# main.net
KiCad netlist of a schematic drawn in Altium Designer
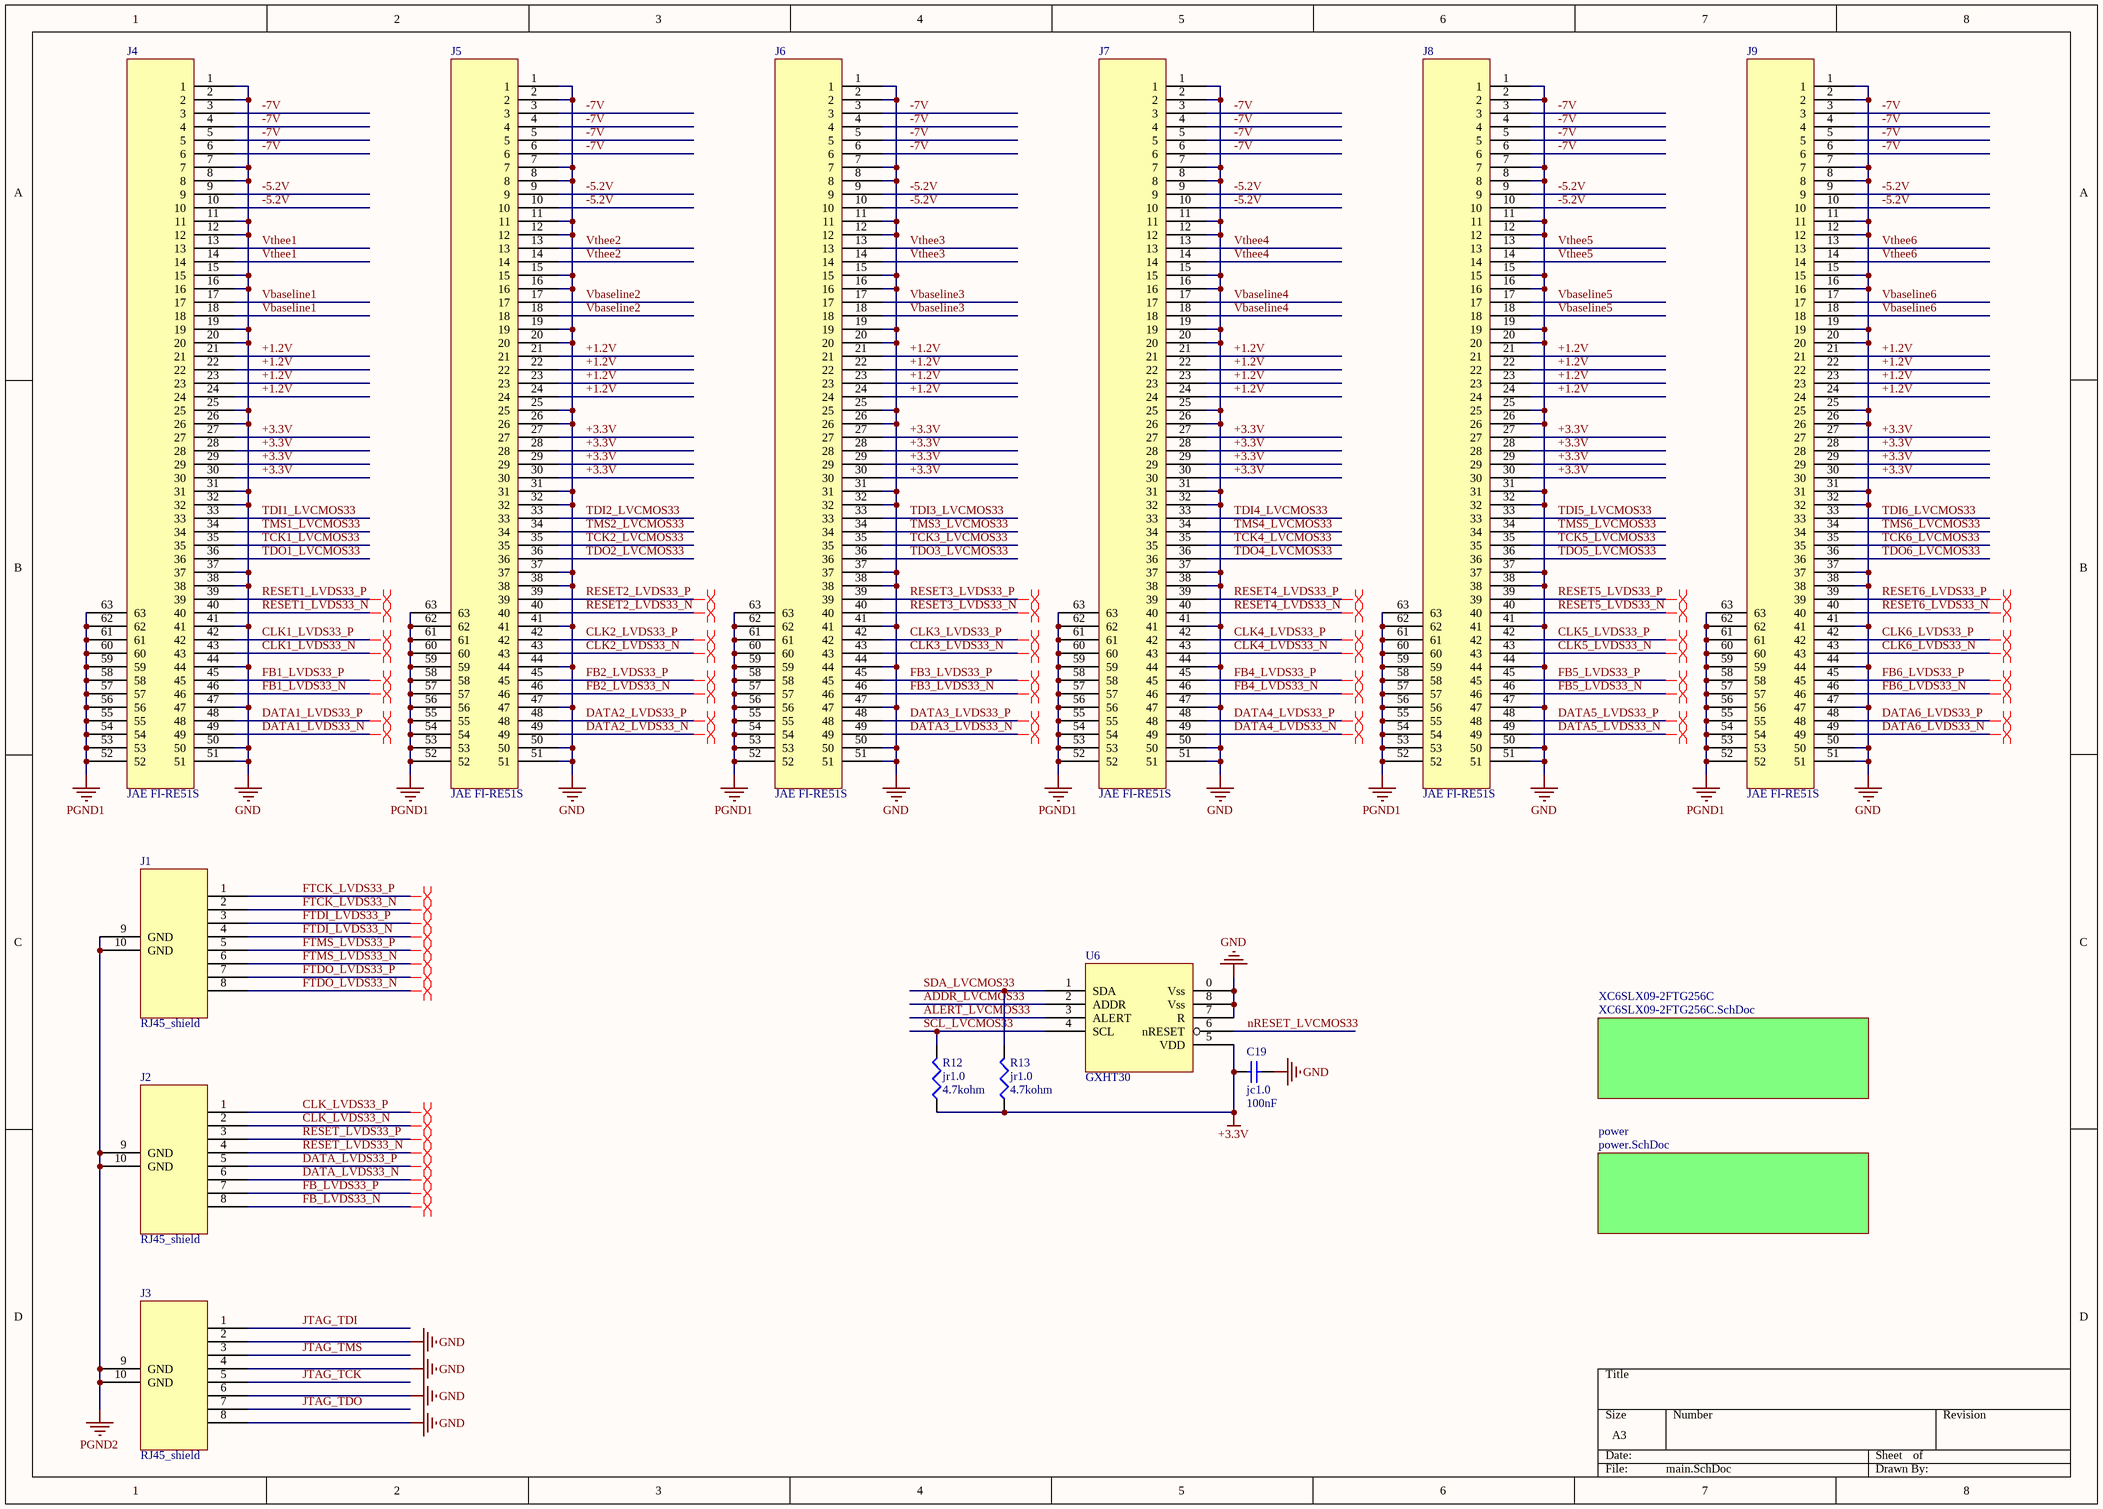
[diagram p0: main.SchDoc]

(export (version "E")
  (design (tool "Eeschema 10.0.6"))
  (components
    (comp (ref "C19")
      (value "jc1.0")
      (footprint "0402")
      (description "Capacitor")
      (fields (field (name "ALTIUM_VALUE") "100nF") (field (name "PUBLISHER") "Altium Limited"))
      (libsource (lib "LIB01DXP2006SchLib") (part "Cap"))
    )
    (comp (ref "J1")
      (value "RJ45_shield")
      (footprint "RJ45_shield")
      (libsource (lib "LIB01DXP2006SchLib") (part "RJ45_shield"))
    )
    (comp (ref "J2")
      (value "RJ45_shield")
      (footprint "RJ45_shield")
      (libsource (lib "LIB01DXP2006SchLib") (part "RJ45_shield"))
    )
    (comp (ref "J3")
      (value "RJ45_shield")
      (footprint "RJ45_shield")
      (libsource (lib "LIB01DXP2006SchLib") (part "RJ45_shield"))
    )
    (comp (ref "J4")
      (value "JAE FI-RE51S")
      (footprint "FI-RE51S-VF")
      (libsource (lib "LIB01DXP2006SchLib") (part "JAE FI-RE51S"))
    )
    (comp (ref "J5")
      (value "JAE FI-RE51S")
      (footprint "FI-RE51S-VF")
      (libsource (lib "LIB01DXP2006SchLib") (part "JAE FI-RE51S"))
    )
    (comp (ref "J6")
      (value "JAE FI-RE51S")
      (footprint "FI-RE51S-VF")
      (libsource (lib "LIB01DXP2006SchLib") (part "JAE FI-RE51S"))
    )
    (comp (ref "J7")
      (value "JAE FI-RE51S")
      (footprint "FI-RE51S-VF")
      (libsource (lib "LIB01DXP2006SchLib") (part "JAE FI-RE51S"))
    )
    (comp (ref "J8")
      (value "JAE FI-RE51S")
      (footprint "FI-RE51S-VF")
      (libsource (lib "LIB01DXP2006SchLib") (part "JAE FI-RE51S"))
    )
    (comp (ref "J9")
      (value "JAE FI-RE51S")
      (footprint "FI-RE51S-VF")
      (libsource (lib "LIB01DXP2006SchLib") (part "JAE FI-RE51S"))
    )
    (comp (ref "R12")
      (value "jr1.0")
      (footprint "0402")
      (description "Resistor")
      (fields (field (name "ALTIUM_VALUE") "4.7kohm") (field (name "PUBLISHER") "Altium Limited"))
      (libsource (lib "LIB01DXP2006SchLib") (part "Res"))
    )
    (comp (ref "R13")
      (value "jr1.0")
      (footprint "0402")
      (description "Resistor")
      (fields (field (name "ALTIUM_VALUE") "4.7kohm") (field (name "PUBLISHER") "Altium Limited"))
      (libsource (lib "LIB01DXP2006SchLib") (part "Res"))
    )
    (comp (ref "U6")
      (value "GXHT30")
      (footprint "GXHT30")
      (libsource (lib "LIB01DXP2006SchLib") (part "GXHT30"))
    )
  )
  (nets
    (net (code "1") (name "+3.3V") (class "Default")
      (node (ref "C19") (pin "1") (pinfunction "1_1") (pintype "passive"))
      (node (ref "J4") (pin "27") (pinfunction "27_27") (pintype "passive"))
      (node (ref "J4") (pin "28") (pinfunction "28_28") (pintype "passive"))
      (node (ref "J4") (pin "29") (pinfunction "29_29") (pintype "passive"))
      (node (ref "J4") (pin "30") (pinfunction "30_30") (pintype "passive"))
      (node (ref "J5") (pin "27") (pinfunction "27_27") (pintype "passive"))
      (node (ref "J5") (pin "28") (pinfunction "28_28") (pintype "passive"))
      (node (ref "J5") (pin "29") (pinfunction "29_29") (pintype "passive"))
      (node (ref "J5") (pin "30") (pinfunction "30_30") (pintype "passive"))
      (node (ref "J6") (pin "27") (pinfunction "27_27") (pintype "passive"))
      (node (ref "J6") (pin "28") (pinfunction "28_28") (pintype "passive"))
      (node (ref "J6") (pin "29") (pinfunction "29_29") (pintype "passive"))
      (node (ref "J6") (pin "30") (pinfunction "30_30") (pintype "passive"))
      (node (ref "J7") (pin "27") (pinfunction "27_27") (pintype "passive"))
      (node (ref "J7") (pin "28") (pinfunction "28_28") (pintype "passive"))
      (node (ref "J7") (pin "29") (pinfunction "29_29") (pintype "passive"))
      (node (ref "J7") (pin "30") (pinfunction "30_30") (pintype "passive"))
      (node (ref "J8") (pin "27") (pinfunction "27_27") (pintype "passive"))
      (node (ref "J8") (pin "28") (pinfunction "28_28") (pintype "passive"))
      (node (ref "J8") (pin "29") (pinfunction "29_29") (pintype "passive"))
      (node (ref "J8") (pin "30") (pinfunction "30_30") (pintype "passive"))
      (node (ref "J9") (pin "27") (pinfunction "27_27") (pintype "passive"))
      (node (ref "J9") (pin "28") (pinfunction "28_28") (pintype "passive"))
      (node (ref "J9") (pin "29") (pinfunction "29_29") (pintype "passive"))
      (node (ref "J9") (pin "30") (pinfunction "30_30") (pintype "passive"))
      (node (ref "R12") (pin "1") (pinfunction "1_1") (pintype "passive"))
      (node (ref "R13") (pin "1") (pinfunction "1_1") (pintype "passive"))
      (node (ref "U6") (pin "5") (pinfunction "VDD_5") (pintype "passive"))
    )
    (net (code "2") (name "/+1.2V") (class "Default")
      (node (ref "J4") (pin "21") (pinfunction "21_21") (pintype "passive"))
      (node (ref "J4") (pin "22") (pinfunction "22_22") (pintype "passive"))
      (node (ref "J4") (pin "23") (pinfunction "23_23") (pintype "passive"))
      (node (ref "J4") (pin "24") (pinfunction "24_24") (pintype "passive"))
      (node (ref "J5") (pin "21") (pinfunction "21_21") (pintype "passive"))
      (node (ref "J5") (pin "22") (pinfunction "22_22") (pintype "passive"))
      (node (ref "J5") (pin "23") (pinfunction "23_23") (pintype "passive"))
      (node (ref "J5") (pin "24") (pinfunction "24_24") (pintype "passive"))
      (node (ref "J6") (pin "21") (pinfunction "21_21") (pintype "passive"))
      (node (ref "J6") (pin "22") (pinfunction "22_22") (pintype "passive"))
      (node (ref "J6") (pin "23") (pinfunction "23_23") (pintype "passive"))
      (node (ref "J6") (pin "24") (pinfunction "24_24") (pintype "passive"))
      (node (ref "J7") (pin "21") (pinfunction "21_21") (pintype "passive"))
      (node (ref "J7") (pin "22") (pinfunction "22_22") (pintype "passive"))
      (node (ref "J7") (pin "23") (pinfunction "23_23") (pintype "passive"))
      (node (ref "J7") (pin "24") (pinfunction "24_24") (pintype "passive"))
      (node (ref "J8") (pin "21") (pinfunction "21_21") (pintype "passive"))
      (node (ref "J8") (pin "22") (pinfunction "22_22") (pintype "passive"))
      (node (ref "J8") (pin "23") (pinfunction "23_23") (pintype "passive"))
      (node (ref "J8") (pin "24") (pinfunction "24_24") (pintype "passive"))
      (node (ref "J9") (pin "21") (pinfunction "21_21") (pintype "passive"))
      (node (ref "J9") (pin "22") (pinfunction "22_22") (pintype "passive"))
      (node (ref "J9") (pin "23") (pinfunction "23_23") (pintype "passive"))
      (node (ref "J9") (pin "24") (pinfunction "24_24") (pintype "passive"))
    )
    (net (code "3") (name "/-5.2V") (class "Default")
      (node (ref "J4") (pin "10") (pinfunction "10_10") (pintype "passive"))
      (node (ref "J4") (pin "9") (pinfunction "9_9") (pintype "passive"))
      (node (ref "J5") (pin "10") (pinfunction "10_10") (pintype "passive"))
      (node (ref "J5") (pin "9") (pinfunction "9_9") (pintype "passive"))
      (node (ref "J6") (pin "10") (pinfunction "10_10") (pintype "passive"))
      (node (ref "J6") (pin "9") (pinfunction "9_9") (pintype "passive"))
      (node (ref "J7") (pin "10") (pinfunction "10_10") (pintype "passive"))
      (node (ref "J7") (pin "9") (pinfunction "9_9") (pintype "passive"))
      (node (ref "J8") (pin "10") (pinfunction "10_10") (pintype "passive"))
      (node (ref "J8") (pin "9") (pinfunction "9_9") (pintype "passive"))
      (node (ref "J9") (pin "10") (pinfunction "10_10") (pintype "passive"))
      (node (ref "J9") (pin "9") (pinfunction "9_9") (pintype "passive"))
    )
    (net (code "4") (name "/-7V") (class "Default")
      (node (ref "J4") (pin "3") (pinfunction "3_3") (pintype "passive"))
      (node (ref "J4") (pin "4") (pinfunction "4_4") (pintype "passive"))
      (node (ref "J4") (pin "5") (pinfunction "5_5") (pintype "passive"))
      (node (ref "J4") (pin "6") (pinfunction "6_6") (pintype "passive"))
      (node (ref "J5") (pin "3") (pinfunction "3_3") (pintype "passive"))
      (node (ref "J5") (pin "4") (pinfunction "4_4") (pintype "passive"))
      (node (ref "J5") (pin "5") (pinfunction "5_5") (pintype "passive"))
      (node (ref "J5") (pin "6") (pinfunction "6_6") (pintype "passive"))
      (node (ref "J6") (pin "3") (pinfunction "3_3") (pintype "passive"))
      (node (ref "J6") (pin "4") (pinfunction "4_4") (pintype "passive"))
      (node (ref "J6") (pin "5") (pinfunction "5_5") (pintype "passive"))
      (node (ref "J6") (pin "6") (pinfunction "6_6") (pintype "passive"))
      (node (ref "J7") (pin "3") (pinfunction "3_3") (pintype "passive"))
      (node (ref "J7") (pin "4") (pinfunction "4_4") (pintype "passive"))
      (node (ref "J7") (pin "5") (pinfunction "5_5") (pintype "passive"))
      (node (ref "J7") (pin "6") (pinfunction "6_6") (pintype "passive"))
      (node (ref "J8") (pin "3") (pinfunction "3_3") (pintype "passive"))
      (node (ref "J8") (pin "4") (pinfunction "4_4") (pintype "passive"))
      (node (ref "J8") (pin "5") (pinfunction "5_5") (pintype "passive"))
      (node (ref "J8") (pin "6") (pinfunction "6_6") (pintype "passive"))
      (node (ref "J9") (pin "3") (pinfunction "3_3") (pintype "passive"))
      (node (ref "J9") (pin "4") (pinfunction "4_4") (pintype "passive"))
      (node (ref "J9") (pin "5") (pinfunction "5_5") (pintype "passive"))
      (node (ref "J9") (pin "6") (pinfunction "6_6") (pintype "passive"))
    )
    (net (code "5") (name "/ADDR_LVCMOS33") (class "Default")
      (node (ref "U6") (pin "2") (pinfunction "ADDR_2") (pintype "passive"))
    )
    (net (code "6") (name "/ALERT_LVCMOS33") (class "Default")
      (node (ref "U6") (pin "3") (pinfunction "ALERT_3") (pintype "passive"))
    )
    (net (code "7") (name "/CLK1_LVDS33_N") (class "Default")
      (node (ref "J4") (pin "43") (pinfunction "43_43") (pintype "passive"))
    )
    (net (code "8") (name "/CLK1_LVDS33_P") (class "Default")
      (node (ref "J4") (pin "42") (pinfunction "42_42") (pintype "passive"))
    )
    (net (code "9") (name "/CLK2_LVDS33_N") (class "Default")
      (node (ref "J5") (pin "43") (pinfunction "43_43") (pintype "passive"))
    )
    (net (code "10") (name "/CLK2_LVDS33_P") (class "Default")
      (node (ref "J5") (pin "42") (pinfunction "42_42") (pintype "passive"))
    )
    (net (code "11") (name "/CLK3_LVDS33_N") (class "Default")
      (node (ref "J6") (pin "43") (pinfunction "43_43") (pintype "passive"))
    )
    (net (code "12") (name "/CLK3_LVDS33_P") (class "Default")
      (node (ref "J6") (pin "42") (pinfunction "42_42") (pintype "passive"))
    )
    (net (code "13") (name "/CLK4_LVDS33_N") (class "Default")
      (node (ref "J7") (pin "43") (pinfunction "43_43") (pintype "passive"))
    )
    (net (code "14") (name "/CLK4_LVDS33_P") (class "Default")
      (node (ref "J7") (pin "42") (pinfunction "42_42") (pintype "passive"))
    )
    (net (code "15") (name "/CLK5_LVDS33_N") (class "Default")
      (node (ref "J8") (pin "43") (pinfunction "43_43") (pintype "passive"))
    )
    (net (code "16") (name "/CLK5_LVDS33_P") (class "Default")
      (node (ref "J8") (pin "42") (pinfunction "42_42") (pintype "passive"))
    )
    (net (code "17") (name "/CLK6_LVDS33_N") (class "Default")
      (node (ref "J9") (pin "43") (pinfunction "43_43") (pintype "passive"))
    )
    (net (code "18") (name "/CLK6_LVDS33_P") (class "Default")
      (node (ref "J9") (pin "42") (pinfunction "42_42") (pintype "passive"))
    )
    (net (code "19") (name "/CLK_LVDS33_N") (class "Default") (node (ref "J2") (pin "2") (pintype "passive")))
    (net (code "20") (name "/CLK_LVDS33_P") (class "Default") (node (ref "J2") (pin "1") (pintype "passive")))
    (net (code "21") (name "/DATA1_LVDS33_N") (class "Default")
      (node (ref "J4") (pin "49") (pinfunction "49_49") (pintype "passive"))
    )
    (net (code "22") (name "/DATA1_LVDS33_P") (class "Default")
      (node (ref "J4") (pin "48") (pinfunction "48_48") (pintype "passive"))
    )
    (net (code "23") (name "/DATA2_LVDS33_N") (class "Default")
      (node (ref "J5") (pin "49") (pinfunction "49_49") (pintype "passive"))
    )
    (net (code "24") (name "/DATA2_LVDS33_P") (class "Default")
      (node (ref "J5") (pin "48") (pinfunction "48_48") (pintype "passive"))
    )
    (net (code "25") (name "/DATA3_LVDS33_N") (class "Default")
      (node (ref "J6") (pin "49") (pinfunction "49_49") (pintype "passive"))
    )
    (net (code "26") (name "/DATA3_LVDS33_P") (class "Default")
      (node (ref "J6") (pin "48") (pinfunction "48_48") (pintype "passive"))
    )
    (net (code "27") (name "/DATA4_LVDS33_N") (class "Default")
      (node (ref "J7") (pin "49") (pinfunction "49_49") (pintype "passive"))
    )
    (net (code "28") (name "/DATA4_LVDS33_P") (class "Default")
      (node (ref "J7") (pin "48") (pinfunction "48_48") (pintype "passive"))
    )
    (net (code "29") (name "/DATA5_LVDS33_N") (class "Default")
      (node (ref "J8") (pin "49") (pinfunction "49_49") (pintype "passive"))
    )
    (net (code "30") (name "/DATA5_LVDS33_P") (class "Default")
      (node (ref "J8") (pin "48") (pinfunction "48_48") (pintype "passive"))
    )
    (net (code "31") (name "/DATA6_LVDS33_N") (class "Default")
      (node (ref "J9") (pin "49") (pinfunction "49_49") (pintype "passive"))
    )
    (net (code "32") (name "/DATA6_LVDS33_P") (class "Default")
      (node (ref "J9") (pin "48") (pinfunction "48_48") (pintype "passive"))
    )
    (net (code "33") (name "/DATA_LVDS33_N") (class "Default")
      (node (ref "J2") (pin "6") (pintype "passive"))
    )
    (net (code "34") (name "/DATA_LVDS33_P") (class "Default")
      (node (ref "J2") (pin "5") (pintype "passive"))
    )
    (net (code "35") (name "/FB1_LVDS33_N") (class "Default")
      (node (ref "J4") (pin "46") (pinfunction "46_46") (pintype "passive"))
    )
    (net (code "36") (name "/FB1_LVDS33_P") (class "Default")
      (node (ref "J4") (pin "45") (pinfunction "45_45") (pintype "passive"))
    )
    (net (code "37") (name "/FB2_LVDS33_N") (class "Default")
      (node (ref "J5") (pin "46") (pinfunction "46_46") (pintype "passive"))
    )
    (net (code "38") (name "/FB2_LVDS33_P") (class "Default")
      (node (ref "J5") (pin "45") (pinfunction "45_45") (pintype "passive"))
    )
    (net (code "39") (name "/FB3_LVDS33_N") (class "Default")
      (node (ref "J6") (pin "46") (pinfunction "46_46") (pintype "passive"))
    )
    (net (code "40") (name "/FB3_LVDS33_P") (class "Default")
      (node (ref "J6") (pin "45") (pinfunction "45_45") (pintype "passive"))
    )
    (net (code "41") (name "/FB4_LVDS33_N") (class "Default")
      (node (ref "J7") (pin "46") (pinfunction "46_46") (pintype "passive"))
    )
    (net (code "42") (name "/FB4_LVDS33_P") (class "Default")
      (node (ref "J7") (pin "45") (pinfunction "45_45") (pintype "passive"))
    )
    (net (code "43") (name "/FB5_LVDS33_N") (class "Default")
      (node (ref "J8") (pin "46") (pinfunction "46_46") (pintype "passive"))
    )
    (net (code "44") (name "/FB5_LVDS33_P") (class "Default")
      (node (ref "J8") (pin "45") (pinfunction "45_45") (pintype "passive"))
    )
    (net (code "45") (name "/FB6_LVDS33_N") (class "Default")
      (node (ref "J9") (pin "46") (pinfunction "46_46") (pintype "passive"))
    )
    (net (code "46") (name "/FB6_LVDS33_P") (class "Default")
      (node (ref "J9") (pin "45") (pinfunction "45_45") (pintype "passive"))
    )
    (net (code "47") (name "/FB_LVDS33_N") (class "Default") (node (ref "J2") (pin "8") (pintype "passive")))
    (net (code "48") (name "/FB_LVDS33_P") (class "Default") (node (ref "J2") (pin "7") (pintype "passive")))
    (net (code "49") (name "/FTCK_LVDS33_N") (class "Default")
      (node (ref "J1") (pin "2") (pintype "passive"))
    )
    (net (code "50") (name "/FTCK_LVDS33_P") (class "Default")
      (node (ref "J1") (pin "1") (pintype "passive"))
    )
    (net (code "51") (name "/FTDI_LVDS33_N") (class "Default")
      (node (ref "J1") (pin "4") (pintype "passive"))
    )
    (net (code "52") (name "/FTDI_LVDS33_P") (class "Default")
      (node (ref "J1") (pin "3") (pintype "passive"))
    )
    (net (code "53") (name "/FTDO_LVDS33_N") (class "Default")
      (node (ref "J1") (pin "8") (pintype "passive"))
    )
    (net (code "54") (name "/FTDO_LVDS33_P") (class "Default")
      (node (ref "J1") (pin "7") (pintype "passive"))
    )
    (net (code "55") (name "/FTMS_LVDS33_N") (class "Default")
      (node (ref "J1") (pin "6") (pintype "passive"))
    )
    (net (code "56") (name "/FTMS_LVDS33_P") (class "Default")
      (node (ref "J1") (pin "5") (pintype "passive"))
    )
    (net (code "57") (name "/JTAG_TCK") (class "Default") (node (ref "J3") (pin "5") (pintype "passive")))
    (net (code "58") (name "/JTAG_TDI") (class "Default") (node (ref "J3") (pin "1") (pintype "passive")))
    (net (code "59") (name "/JTAG_TDO") (class "Default") (node (ref "J3") (pin "7") (pintype "passive")))
    (net (code "60") (name "/JTAG_TMS") (class "Default") (node (ref "J3") (pin "3") (pintype "passive")))
    (net (code "61") (name "/RESET1_LVDS33_N") (class "Default")
      (node (ref "J4") (pin "40") (pinfunction "40_40") (pintype "passive"))
    )
    (net (code "62") (name "/RESET1_LVDS33_P") (class "Default")
      (node (ref "J4") (pin "39") (pinfunction "39_39") (pintype "passive"))
    )
    (net (code "63") (name "/RESET2_LVDS33_N") (class "Default")
      (node (ref "J5") (pin "40") (pinfunction "40_40") (pintype "passive"))
    )
    (net (code "64") (name "/RESET2_LVDS33_P") (class "Default")
      (node (ref "J5") (pin "39") (pinfunction "39_39") (pintype "passive"))
    )
    (net (code "65") (name "/RESET3_LVDS33_N") (class "Default")
      (node (ref "J6") (pin "40") (pinfunction "40_40") (pintype "passive"))
    )
    (net (code "66") (name "/RESET3_LVDS33_P") (class "Default")
      (node (ref "J6") (pin "39") (pinfunction "39_39") (pintype "passive"))
    )
    (net (code "67") (name "/RESET4_LVDS33_N") (class "Default")
      (node (ref "J7") (pin "40") (pinfunction "40_40") (pintype "passive"))
    )
    (net (code "68") (name "/RESET4_LVDS33_P") (class "Default")
      (node (ref "J7") (pin "39") (pinfunction "39_39") (pintype "passive"))
    )
    (net (code "69") (name "/RESET5_LVDS33_N") (class "Default")
      (node (ref "J8") (pin "40") (pinfunction "40_40") (pintype "passive"))
    )
    (net (code "70") (name "/RESET5_LVDS33_P") (class "Default")
      (node (ref "J8") (pin "39") (pinfunction "39_39") (pintype "passive"))
    )
    (net (code "71") (name "/RESET6_LVDS33_N") (class "Default")
      (node (ref "J9") (pin "40") (pinfunction "40_40") (pintype "passive"))
    )
    (net (code "72") (name "/RESET6_LVDS33_P") (class "Default")
      (node (ref "J9") (pin "39") (pinfunction "39_39") (pintype "passive"))
    )
    (net (code "73") (name "/RESET_LVDS33_N") (class "Default")
      (node (ref "J2") (pin "4") (pintype "passive"))
    )
    (net (code "74") (name "/RESET_LVDS33_P") (class "Default")
      (node (ref "J2") (pin "3") (pintype "passive"))
    )
    (net (code "75") (name "/SCL_LVCMOS33") (class "Default")
      (node (ref "R12") (pin "2") (pinfunction "2_2") (pintype "passive"))
      (node (ref "U6") (pin "4") (pinfunction "SCL_4") (pintype "passive"))
    )
    (net (code "76") (name "/SDA_LVCMOS33") (class "Default")
      (node (ref "R13") (pin "2") (pinfunction "2_2") (pintype "passive"))
      (node (ref "U6") (pin "1") (pinfunction "SDA_1") (pintype "passive"))
    )
    (net (code "77") (name "/TCK1_LVCMOS33") (class "Default")
      (node (ref "J4") (pin "35") (pinfunction "35_35") (pintype "passive"))
    )
    (net (code "78") (name "/TCK2_LVCMOS33") (class "Default")
      (node (ref "J5") (pin "35") (pinfunction "35_35") (pintype "passive"))
    )
    (net (code "79") (name "/TCK3_LVCMOS33") (class "Default")
      (node (ref "J6") (pin "35") (pinfunction "35_35") (pintype "passive"))
    )
    (net (code "80") (name "/TCK4_LVCMOS33") (class "Default")
      (node (ref "J7") (pin "35") (pinfunction "35_35") (pintype "passive"))
    )
    (net (code "81") (name "/TCK5_LVCMOS33") (class "Default")
      (node (ref "J8") (pin "35") (pinfunction "35_35") (pintype "passive"))
    )
    (net (code "82") (name "/TCK6_LVCMOS33") (class "Default")
      (node (ref "J9") (pin "35") (pinfunction "35_35") (pintype "passive"))
    )
    (net (code "83") (name "/TDI1_LVCMOS33") (class "Default")
      (node (ref "J4") (pin "33") (pinfunction "33_33") (pintype "passive"))
    )
    (net (code "84") (name "/TDI2_LVCMOS33") (class "Default")
      (node (ref "J5") (pin "33") (pinfunction "33_33") (pintype "passive"))
    )
    (net (code "85") (name "/TDI3_LVCMOS33") (class "Default")
      (node (ref "J6") (pin "33") (pinfunction "33_33") (pintype "passive"))
    )
    (net (code "86") (name "/TDI4_LVCMOS33") (class "Default")
      (node (ref "J7") (pin "33") (pinfunction "33_33") (pintype "passive"))
    )
    (net (code "87") (name "/TDI5_LVCMOS33") (class "Default")
      (node (ref "J8") (pin "33") (pinfunction "33_33") (pintype "passive"))
    )
    (net (code "88") (name "/TDI6_LVCMOS33") (class "Default")
      (node (ref "J9") (pin "33") (pinfunction "33_33") (pintype "passive"))
    )
    (net (code "89") (name "/TDO1_LVCMOS33") (class "Default")
      (node (ref "J4") (pin "36") (pinfunction "36_36") (pintype "passive"))
    )
    (net (code "90") (name "/TDO2_LVCMOS33") (class "Default")
      (node (ref "J5") (pin "36") (pinfunction "36_36") (pintype "passive"))
    )
    (net (code "91") (name "/TDO3_LVCMOS33") (class "Default")
      (node (ref "J6") (pin "36") (pinfunction "36_36") (pintype "passive"))
    )
    (net (code "92") (name "/TDO4_LVCMOS33") (class "Default")
      (node (ref "J7") (pin "36") (pinfunction "36_36") (pintype "passive"))
    )
    (net (code "93") (name "/TDO5_LVCMOS33") (class "Default")
      (node (ref "J8") (pin "36") (pinfunction "36_36") (pintype "passive"))
    )
    (net (code "94") (name "/TDO6_LVCMOS33") (class "Default")
      (node (ref "J9") (pin "36") (pinfunction "36_36") (pintype "passive"))
    )
    (net (code "95") (name "/TMS1_LVCMOS33") (class "Default")
      (node (ref "J4") (pin "34") (pinfunction "34_34") (pintype "passive"))
    )
    (net (code "96") (name "/TMS2_LVCMOS33") (class "Default")
      (node (ref "J5") (pin "34") (pinfunction "34_34") (pintype "passive"))
    )
    (net (code "97") (name "/TMS3_LVCMOS33") (class "Default")
      (node (ref "J6") (pin "34") (pinfunction "34_34") (pintype "passive"))
    )
    (net (code "98") (name "/TMS4_LVCMOS33") (class "Default")
      (node (ref "J7") (pin "34") (pinfunction "34_34") (pintype "passive"))
    )
    (net (code "99") (name "/TMS5_LVCMOS33") (class "Default")
      (node (ref "J8") (pin "34") (pinfunction "34_34") (pintype "passive"))
    )
    (net (code "100") (name "/TMS6_LVCMOS33") (class "Default")
      (node (ref "J9") (pin "34") (pinfunction "34_34") (pintype "passive"))
    )
    (net (code "101") (name "/Vbaseline1") (class "Default")
      (node (ref "J4") (pin "17") (pinfunction "17_17") (pintype "passive"))
      (node (ref "J4") (pin "18") (pinfunction "18_18") (pintype "passive"))
    )
    (net (code "102") (name "/Vbaseline2") (class "Default")
      (node (ref "J5") (pin "17") (pinfunction "17_17") (pintype "passive"))
      (node (ref "J5") (pin "18") (pinfunction "18_18") (pintype "passive"))
    )
    (net (code "103") (name "/Vbaseline3") (class "Default")
      (node (ref "J6") (pin "17") (pinfunction "17_17") (pintype "passive"))
      (node (ref "J6") (pin "18") (pinfunction "18_18") (pintype "passive"))
    )
    (net (code "104") (name "/Vbaseline4") (class "Default")
      (node (ref "J7") (pin "17") (pinfunction "17_17") (pintype "passive"))
      (node (ref "J7") (pin "18") (pinfunction "18_18") (pintype "passive"))
    )
    (net (code "105") (name "/Vbaseline5") (class "Default")
      (node (ref "J8") (pin "17") (pinfunction "17_17") (pintype "passive"))
      (node (ref "J8") (pin "18") (pinfunction "18_18") (pintype "passive"))
    )
    (net (code "106") (name "/Vbaseline6") (class "Default")
      (node (ref "J9") (pin "17") (pinfunction "17_17") (pintype "passive"))
      (node (ref "J9") (pin "18") (pinfunction "18_18") (pintype "passive"))
    )
    (net (code "107") (name "/Vthee1") (class "Default")
      (node (ref "J4") (pin "13") (pinfunction "13_13") (pintype "passive"))
      (node (ref "J4") (pin "14") (pinfunction "14_14") (pintype "passive"))
    )
    (net (code "108") (name "/Vthee2") (class "Default")
      (node (ref "J5") (pin "13") (pinfunction "13_13") (pintype "passive"))
      (node (ref "J5") (pin "14") (pinfunction "14_14") (pintype "passive"))
    )
    (net (code "109") (name "/Vthee3") (class "Default")
      (node (ref "J6") (pin "13") (pinfunction "13_13") (pintype "passive"))
      (node (ref "J6") (pin "14") (pinfunction "14_14") (pintype "passive"))
    )
    (net (code "110") (name "/Vthee4") (class "Default")
      (node (ref "J7") (pin "13") (pinfunction "13_13") (pintype "passive"))
      (node (ref "J7") (pin "14") (pinfunction "14_14") (pintype "passive"))
    )
    (net (code "111") (name "/Vthee5") (class "Default")
      (node (ref "J8") (pin "13") (pinfunction "13_13") (pintype "passive"))
      (node (ref "J8") (pin "14") (pinfunction "14_14") (pintype "passive"))
    )
    (net (code "112") (name "/Vthee6") (class "Default")
      (node (ref "J9") (pin "13") (pinfunction "13_13") (pintype "passive"))
      (node (ref "J9") (pin "14") (pinfunction "14_14") (pintype "passive"))
    )
    (net (code "113") (name "/nRESET_LVCMOS33") (class "Default")
      (node (ref "U6") (pin "6") (pinfunction "nRESET_6") (pintype "passive"))
    )
    (net (code "114") (name "GND") (class "Default")
      (node (ref "C19") (pin "2") (pinfunction "2_2") (pintype "passive"))
      (node (ref "J3") (pin "2") (pintype "passive"))
      (node (ref "J3") (pin "4") (pintype "passive"))
      (node (ref "J3") (pin "6") (pintype "passive"))
      (node (ref "J3") (pin "8") (pintype "passive"))
      (node (ref "J4") (pin "1") (pinfunction "1_1") (pintype "passive"))
      (node (ref "J4") (pin "11") (pinfunction "11_11") (pintype "passive"))
      (node (ref "J4") (pin "12") (pinfunction "12_12") (pintype "passive"))
      (node (ref "J4") (pin "15") (pinfunction "15_15") (pintype "passive"))
      (node (ref "J4") (pin "16") (pinfunction "16_16") (pintype "passive"))
      (node (ref "J4") (pin "19") (pinfunction "19_19") (pintype "passive"))
      (node (ref "J4") (pin "2") (pinfunction "2_2") (pintype "passive"))
      (node (ref "J4") (pin "20") (pinfunction "20_20") (pintype "passive"))
      (node (ref "J4") (pin "25") (pinfunction "25_25") (pintype "passive"))
      (node (ref "J4") (pin "26") (pinfunction "26_26") (pintype "passive"))
      (node (ref "J4") (pin "31") (pinfunction "31_31") (pintype "passive"))
      (node (ref "J4") (pin "32") (pinfunction "32_32") (pintype "passive"))
      (node (ref "J4") (pin "37") (pinfunction "37_37") (pintype "passive"))
      (node (ref "J4") (pin "38") (pinfunction "38_38") (pintype "passive"))
      (node (ref "J4") (pin "41") (pinfunction "41_41") (pintype "passive"))
      (node (ref "J4") (pin "44") (pinfunction "44_44") (pintype "passive"))
      (node (ref "J4") (pin "47") (pinfunction "47_47") (pintype "passive"))
      (node (ref "J4") (pin "50") (pinfunction "50_50") (pintype "passive"))
      (node (ref "J4") (pin "51") (pinfunction "51_51") (pintype "passive"))
      (node (ref "J4") (pin "7") (pinfunction "7_7") (pintype "passive"))
      (node (ref "J4") (pin "8") (pinfunction "8_8") (pintype "passive"))
      (node (ref "J5") (pin "1") (pinfunction "1_1") (pintype "passive"))
      (node (ref "J5") (pin "11") (pinfunction "11_11") (pintype "passive"))
      (node (ref "J5") (pin "12") (pinfunction "12_12") (pintype "passive"))
      (node (ref "J5") (pin "15") (pinfunction "15_15") (pintype "passive"))
      (node (ref "J5") (pin "16") (pinfunction "16_16") (pintype "passive"))
      (node (ref "J5") (pin "19") (pinfunction "19_19") (pintype "passive"))
      (node (ref "J5") (pin "2") (pinfunction "2_2") (pintype "passive"))
      (node (ref "J5") (pin "20") (pinfunction "20_20") (pintype "passive"))
      (node (ref "J5") (pin "25") (pinfunction "25_25") (pintype "passive"))
      (node (ref "J5") (pin "26") (pinfunction "26_26") (pintype "passive"))
      (node (ref "J5") (pin "31") (pinfunction "31_31") (pintype "passive"))
      (node (ref "J5") (pin "32") (pinfunction "32_32") (pintype "passive"))
      (node (ref "J5") (pin "37") (pinfunction "37_37") (pintype "passive"))
      (node (ref "J5") (pin "38") (pinfunction "38_38") (pintype "passive"))
      (node (ref "J5") (pin "41") (pinfunction "41_41") (pintype "passive"))
      (node (ref "J5") (pin "44") (pinfunction "44_44") (pintype "passive"))
      (node (ref "J5") (pin "47") (pinfunction "47_47") (pintype "passive"))
      (node (ref "J5") (pin "50") (pinfunction "50_50") (pintype "passive"))
      (node (ref "J5") (pin "51") (pinfunction "51_51") (pintype "passive"))
      (node (ref "J5") (pin "7") (pinfunction "7_7") (pintype "passive"))
      (node (ref "J5") (pin "8") (pinfunction "8_8") (pintype "passive"))
      (node (ref "J6") (pin "1") (pinfunction "1_1") (pintype "passive"))
      (node (ref "J6") (pin "11") (pinfunction "11_11") (pintype "passive"))
      (node (ref "J6") (pin "12") (pinfunction "12_12") (pintype "passive"))
      (node (ref "J6") (pin "15") (pinfunction "15_15") (pintype "passive"))
      (node (ref "J6") (pin "16") (pinfunction "16_16") (pintype "passive"))
      (node (ref "J6") (pin "19") (pinfunction "19_19") (pintype "passive"))
      (node (ref "J6") (pin "2") (pinfunction "2_2") (pintype "passive"))
      (node (ref "J6") (pin "20") (pinfunction "20_20") (pintype "passive"))
      (node (ref "J6") (pin "25") (pinfunction "25_25") (pintype "passive"))
      (node (ref "J6") (pin "26") (pinfunction "26_26") (pintype "passive"))
      (node (ref "J6") (pin "31") (pinfunction "31_31") (pintype "passive"))
      (node (ref "J6") (pin "32") (pinfunction "32_32") (pintype "passive"))
      (node (ref "J6") (pin "37") (pinfunction "37_37") (pintype "passive"))
      (node (ref "J6") (pin "38") (pinfunction "38_38") (pintype "passive"))
      (node (ref "J6") (pin "41") (pinfunction "41_41") (pintype "passive"))
      (node (ref "J6") (pin "44") (pinfunction "44_44") (pintype "passive"))
      (node (ref "J6") (pin "47") (pinfunction "47_47") (pintype "passive"))
      (node (ref "J6") (pin "50") (pinfunction "50_50") (pintype "passive"))
      (node (ref "J6") (pin "51") (pinfunction "51_51") (pintype "passive"))
      (node (ref "J6") (pin "7") (pinfunction "7_7") (pintype "passive"))
      (node (ref "J6") (pin "8") (pinfunction "8_8") (pintype "passive"))
      (node (ref "J7") (pin "1") (pinfunction "1_1") (pintype "passive"))
      (node (ref "J7") (pin "11") (pinfunction "11_11") (pintype "passive"))
      (node (ref "J7") (pin "12") (pinfunction "12_12") (pintype "passive"))
      (node (ref "J7") (pin "15") (pinfunction "15_15") (pintype "passive"))
      (node (ref "J7") (pin "16") (pinfunction "16_16") (pintype "passive"))
      (node (ref "J7") (pin "19") (pinfunction "19_19") (pintype "passive"))
      (node (ref "J7") (pin "2") (pinfunction "2_2") (pintype "passive"))
      (node (ref "J7") (pin "20") (pinfunction "20_20") (pintype "passive"))
      (node (ref "J7") (pin "25") (pinfunction "25_25") (pintype "passive"))
      (node (ref "J7") (pin "26") (pinfunction "26_26") (pintype "passive"))
      (node (ref "J7") (pin "31") (pinfunction "31_31") (pintype "passive"))
      (node (ref "J7") (pin "32") (pinfunction "32_32") (pintype "passive"))
      (node (ref "J7") (pin "37") (pinfunction "37_37") (pintype "passive"))
      (node (ref "J7") (pin "38") (pinfunction "38_38") (pintype "passive"))
      (node (ref "J7") (pin "41") (pinfunction "41_41") (pintype "passive"))
      (node (ref "J7") (pin "44") (pinfunction "44_44") (pintype "passive"))
      (node (ref "J7") (pin "47") (pinfunction "47_47") (pintype "passive"))
      (node (ref "J7") (pin "50") (pinfunction "50_50") (pintype "passive"))
      (node (ref "J7") (pin "51") (pinfunction "51_51") (pintype "passive"))
      (node (ref "J7") (pin "7") (pinfunction "7_7") (pintype "passive"))
      (node (ref "J7") (pin "8") (pinfunction "8_8") (pintype "passive"))
      (node (ref "J8") (pin "1") (pinfunction "1_1") (pintype "passive"))
      (node (ref "J8") (pin "11") (pinfunction "11_11") (pintype "passive"))
      (node (ref "J8") (pin "12") (pinfunction "12_12") (pintype "passive"))
      (node (ref "J8") (pin "15") (pinfunction "15_15") (pintype "passive"))
      (node (ref "J8") (pin "16") (pinfunction "16_16") (pintype "passive"))
      (node (ref "J8") (pin "19") (pinfunction "19_19") (pintype "passive"))
      (node (ref "J8") (pin "2") (pinfunction "2_2") (pintype "passive"))
      (node (ref "J8") (pin "20") (pinfunction "20_20") (pintype "passive"))
      (node (ref "J8") (pin "25") (pinfunction "25_25") (pintype "passive"))
      (node (ref "J8") (pin "26") (pinfunction "26_26") (pintype "passive"))
      (node (ref "J8") (pin "31") (pinfunction "31_31") (pintype "passive"))
      (node (ref "J8") (pin "32") (pinfunction "32_32") (pintype "passive"))
      (node (ref "J8") (pin "37") (pinfunction "37_37") (pintype "passive"))
      (node (ref "J8") (pin "38") (pinfunction "38_38") (pintype "passive"))
      (node (ref "J8") (pin "41") (pinfunction "41_41") (pintype "passive"))
      (node (ref "J8") (pin "44") (pinfunction "44_44") (pintype "passive"))
      (node (ref "J8") (pin "47") (pinfunction "47_47") (pintype "passive"))
      (node (ref "J8") (pin "50") (pinfunction "50_50") (pintype "passive"))
      (node (ref "J8") (pin "51") (pinfunction "51_51") (pintype "passive"))
      (node (ref "J8") (pin "7") (pinfunction "7_7") (pintype "passive"))
      (node (ref "J8") (pin "8") (pinfunction "8_8") (pintype "passive"))
      (node (ref "J9") (pin "1") (pinfunction "1_1") (pintype "passive"))
      (node (ref "J9") (pin "11") (pinfunction "11_11") (pintype "passive"))
      (node (ref "J9") (pin "12") (pinfunction "12_12") (pintype "passive"))
      (node (ref "J9") (pin "15") (pinfunction "15_15") (pintype "passive"))
      (node (ref "J9") (pin "16") (pinfunction "16_16") (pintype "passive"))
      (node (ref "J9") (pin "19") (pinfunction "19_19") (pintype "passive"))
      (node (ref "J9") (pin "2") (pinfunction "2_2") (pintype "passive"))
      (node (ref "J9") (pin "20") (pinfunction "20_20") (pintype "passive"))
      (node (ref "J9") (pin "25") (pinfunction "25_25") (pintype "passive"))
      (node (ref "J9") (pin "26") (pinfunction "26_26") (pintype "passive"))
      (node (ref "J9") (pin "31") (pinfunction "31_31") (pintype "passive"))
      (node (ref "J9") (pin "32") (pinfunction "32_32") (pintype "passive"))
      (node (ref "J9") (pin "37") (pinfunction "37_37") (pintype "passive"))
      (node (ref "J9") (pin "38") (pinfunction "38_38") (pintype "passive"))
      (node (ref "J9") (pin "41") (pinfunction "41_41") (pintype "passive"))
      (node (ref "J9") (pin "44") (pinfunction "44_44") (pintype "passive"))
      (node (ref "J9") (pin "47") (pinfunction "47_47") (pintype "passive"))
      (node (ref "J9") (pin "50") (pinfunction "50_50") (pintype "passive"))
      (node (ref "J9") (pin "51") (pinfunction "51_51") (pintype "passive"))
      (node (ref "J9") (pin "7") (pinfunction "7_7") (pintype "passive"))
      (node (ref "J9") (pin "8") (pinfunction "8_8") (pintype "passive"))
      (node (ref "U6") (pin "0") (pinfunction "Vss_0") (pintype "passive"))
      (node (ref "U6") (pin "7") (pinfunction "R_7") (pintype "passive"))
      (node (ref "U6") (pin "8") (pinfunction "Vss_8") (pintype "passive"))
    )
    (net (code "115") (name "PGND1") (class "Default")
      (node (ref "J4") (pin "52") (pinfunction "52_52") (pintype "passive"))
      (node (ref "J4") (pin "53") (pinfunction "53_53") (pintype "passive"))
      (node (ref "J4") (pin "54") (pinfunction "54_54") (pintype "passive"))
      (node (ref "J4") (pin "55") (pinfunction "55_55") (pintype "passive"))
      (node (ref "J4") (pin "56") (pinfunction "56_56") (pintype "passive"))
      (node (ref "J4") (pin "57") (pinfunction "57_57") (pintype "passive"))
      (node (ref "J4") (pin "58") (pinfunction "58_58") (pintype "passive"))
      (node (ref "J4") (pin "59") (pinfunction "59_59") (pintype "passive"))
      (node (ref "J4") (pin "60") (pinfunction "60_60") (pintype "passive"))
      (node (ref "J4") (pin "61") (pinfunction "61_61") (pintype "passive"))
      (node (ref "J4") (pin "62") (pinfunction "62_62") (pintype "passive"))
      (node (ref "J4") (pin "63") (pinfunction "63_63") (pintype "passive"))
      (node (ref "J5") (pin "52") (pinfunction "52_52") (pintype "passive"))
      (node (ref "J5") (pin "53") (pinfunction "53_53") (pintype "passive"))
      (node (ref "J5") (pin "54") (pinfunction "54_54") (pintype "passive"))
      (node (ref "J5") (pin "55") (pinfunction "55_55") (pintype "passive"))
      (node (ref "J5") (pin "56") (pinfunction "56_56") (pintype "passive"))
      (node (ref "J5") (pin "57") (pinfunction "57_57") (pintype "passive"))
      (node (ref "J5") (pin "58") (pinfunction "58_58") (pintype "passive"))
      (node (ref "J5") (pin "59") (pinfunction "59_59") (pintype "passive"))
      (node (ref "J5") (pin "60") (pinfunction "60_60") (pintype "passive"))
      (node (ref "J5") (pin "61") (pinfunction "61_61") (pintype "passive"))
      (node (ref "J5") (pin "62") (pinfunction "62_62") (pintype "passive"))
      (node (ref "J5") (pin "63") (pinfunction "63_63") (pintype "passive"))
      (node (ref "J6") (pin "52") (pinfunction "52_52") (pintype "passive"))
      (node (ref "J6") (pin "53") (pinfunction "53_53") (pintype "passive"))
      (node (ref "J6") (pin "54") (pinfunction "54_54") (pintype "passive"))
      (node (ref "J6") (pin "55") (pinfunction "55_55") (pintype "passive"))
      (node (ref "J6") (pin "56") (pinfunction "56_56") (pintype "passive"))
      (node (ref "J6") (pin "57") (pinfunction "57_57") (pintype "passive"))
      (node (ref "J6") (pin "58") (pinfunction "58_58") (pintype "passive"))
      (node (ref "J6") (pin "59") (pinfunction "59_59") (pintype "passive"))
      (node (ref "J6") (pin "60") (pinfunction "60_60") (pintype "passive"))
      (node (ref "J6") (pin "61") (pinfunction "61_61") (pintype "passive"))
      (node (ref "J6") (pin "62") (pinfunction "62_62") (pintype "passive"))
      (node (ref "J6") (pin "63") (pinfunction "63_63") (pintype "passive"))
      (node (ref "J7") (pin "52") (pinfunction "52_52") (pintype "passive"))
      (node (ref "J7") (pin "53") (pinfunction "53_53") (pintype "passive"))
      (node (ref "J7") (pin "54") (pinfunction "54_54") (pintype "passive"))
      (node (ref "J7") (pin "55") (pinfunction "55_55") (pintype "passive"))
      (node (ref "J7") (pin "56") (pinfunction "56_56") (pintype "passive"))
      (node (ref "J7") (pin "57") (pinfunction "57_57") (pintype "passive"))
      (node (ref "J7") (pin "58") (pinfunction "58_58") (pintype "passive"))
      (node (ref "J7") (pin "59") (pinfunction "59_59") (pintype "passive"))
      (node (ref "J7") (pin "60") (pinfunction "60_60") (pintype "passive"))
      (node (ref "J7") (pin "61") (pinfunction "61_61") (pintype "passive"))
      (node (ref "J7") (pin "62") (pinfunction "62_62") (pintype "passive"))
      (node (ref "J7") (pin "63") (pinfunction "63_63") (pintype "passive"))
      (node (ref "J8") (pin "52") (pinfunction "52_52") (pintype "passive"))
      (node (ref "J8") (pin "53") (pinfunction "53_53") (pintype "passive"))
      (node (ref "J8") (pin "54") (pinfunction "54_54") (pintype "passive"))
      (node (ref "J8") (pin "55") (pinfunction "55_55") (pintype "passive"))
      (node (ref "J8") (pin "56") (pinfunction "56_56") (pintype "passive"))
      (node (ref "J8") (pin "57") (pinfunction "57_57") (pintype "passive"))
      (node (ref "J8") (pin "58") (pinfunction "58_58") (pintype "passive"))
      (node (ref "J8") (pin "59") (pinfunction "59_59") (pintype "passive"))
      (node (ref "J8") (pin "60") (pinfunction "60_60") (pintype "passive"))
      (node (ref "J8") (pin "61") (pinfunction "61_61") (pintype "passive"))
      (node (ref "J8") (pin "62") (pinfunction "62_62") (pintype "passive"))
      (node (ref "J8") (pin "63") (pinfunction "63_63") (pintype "passive"))
      (node (ref "J9") (pin "52") (pinfunction "52_52") (pintype "passive"))
      (node (ref "J9") (pin "53") (pinfunction "53_53") (pintype "passive"))
      (node (ref "J9") (pin "54") (pinfunction "54_54") (pintype "passive"))
      (node (ref "J9") (pin "55") (pinfunction "55_55") (pintype "passive"))
      (node (ref "J9") (pin "56") (pinfunction "56_56") (pintype "passive"))
      (node (ref "J9") (pin "57") (pinfunction "57_57") (pintype "passive"))
      (node (ref "J9") (pin "58") (pinfunction "58_58") (pintype "passive"))
      (node (ref "J9") (pin "59") (pinfunction "59_59") (pintype "passive"))
      (node (ref "J9") (pin "60") (pinfunction "60_60") (pintype "passive"))
      (node (ref "J9") (pin "61") (pinfunction "61_61") (pintype "passive"))
      (node (ref "J9") (pin "62") (pinfunction "62_62") (pintype "passive"))
      (node (ref "J9") (pin "63") (pinfunction "63_63") (pintype "passive"))
    )
    (net (code "116") (name "PGND2") (class "Default")
      (node (ref "J1") (pin "10") (pinfunction "GND_10") (pintype "passive"))
      (node (ref "J1") (pin "9") (pinfunction "GND_9") (pintype "passive"))
      (node (ref "J2") (pin "10") (pinfunction "GND_10") (pintype "passive"))
      (node (ref "J2") (pin "9") (pinfunction "GND_9") (pintype "passive"))
      (node (ref "J3") (pin "10") (pinfunction "GND_10") (pintype "passive"))
      (node (ref "J3") (pin "9") (pinfunction "GND_9") (pintype "passive"))
    )
  )
)
